# AgnusAdaptorv2.net
KiCad netlist of a schematic drawn in EAGLE
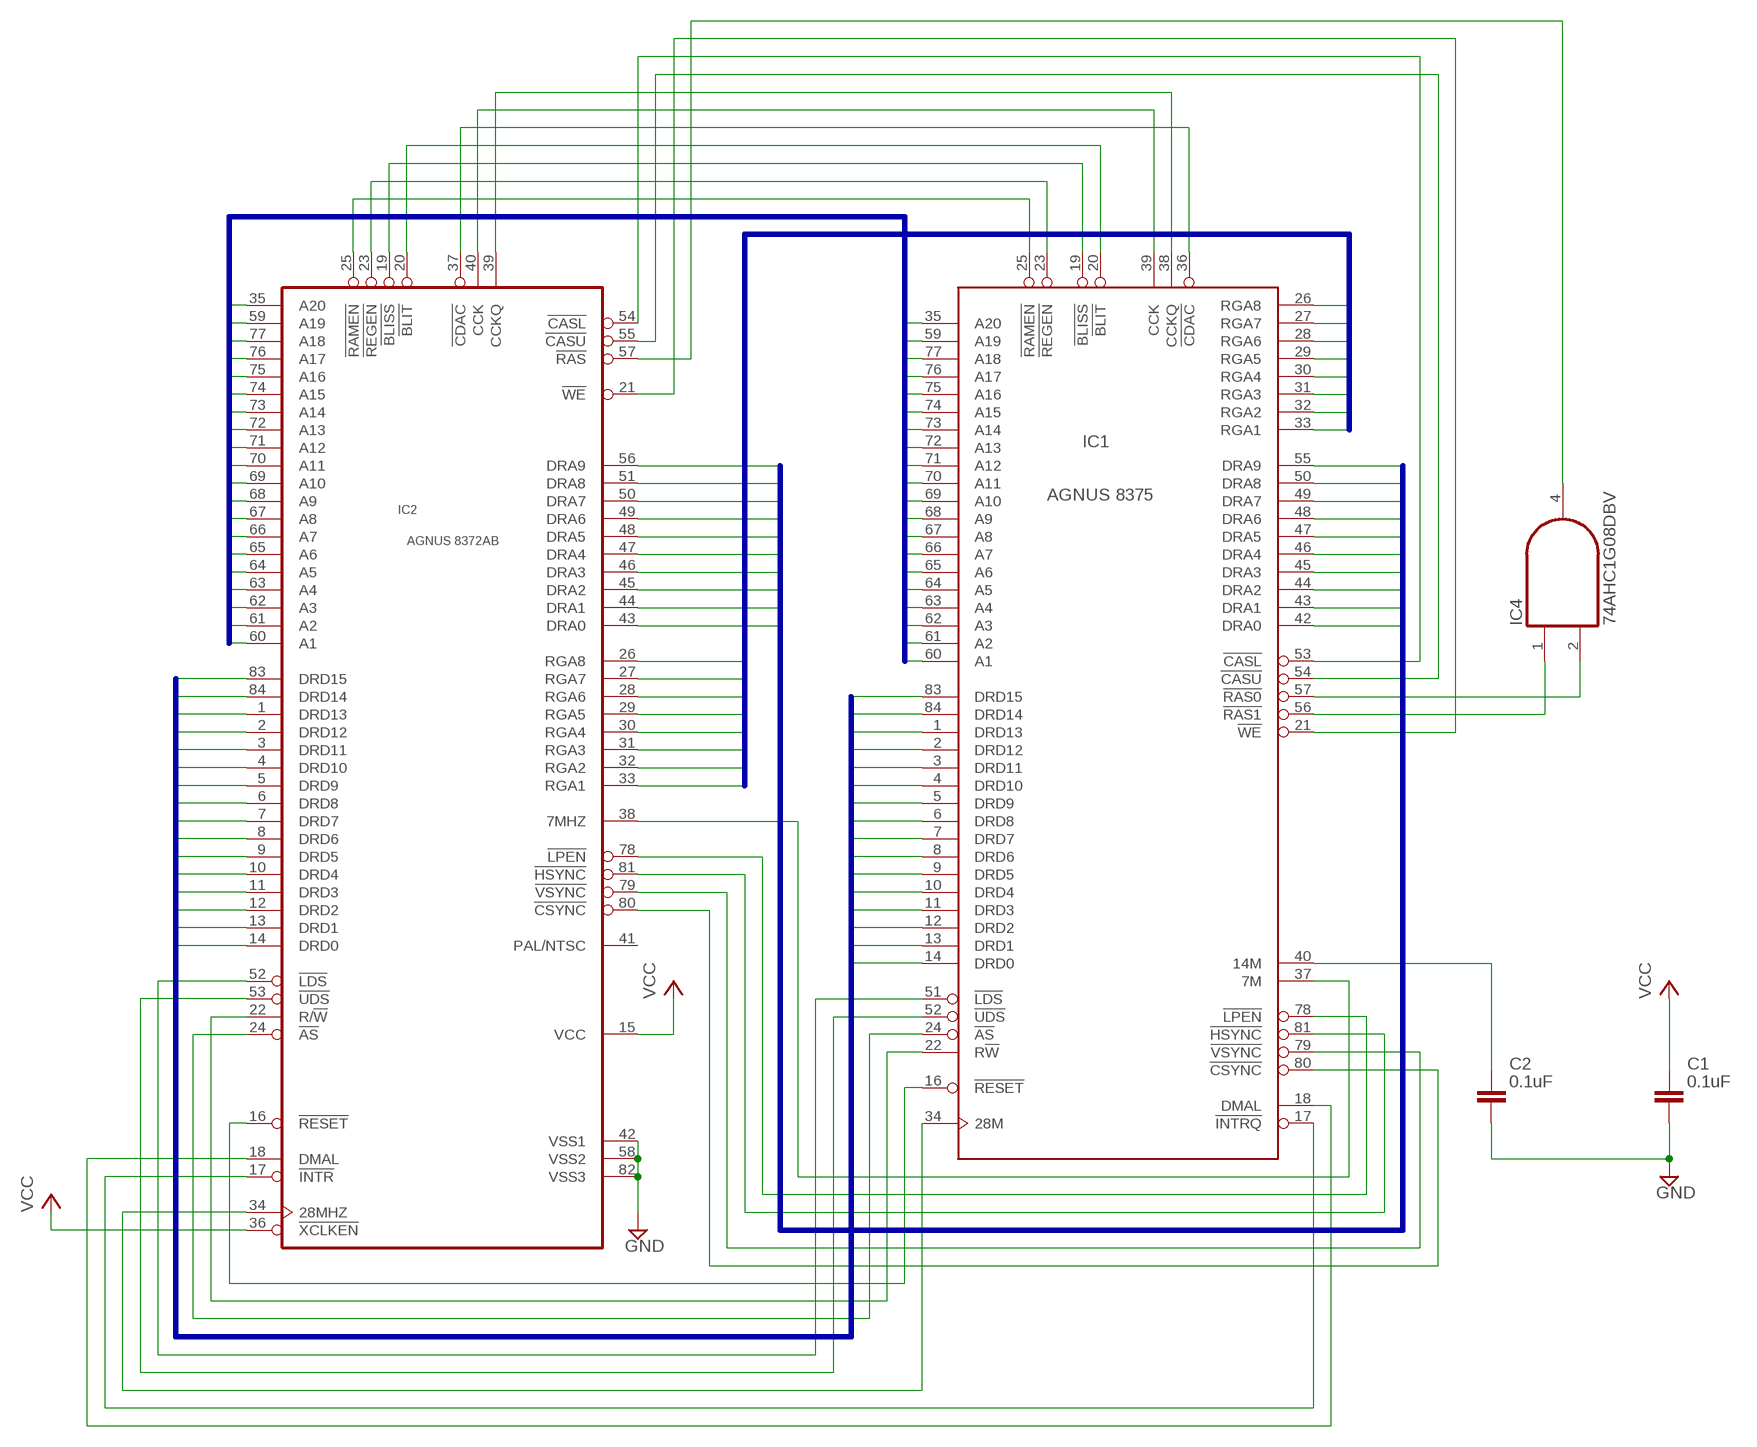
[diagram p0: schematic, sheet 1]

(export (version "E")
  (design (tool "Eeschema 10.0.6"))
  (components
    (comp (ref "C1")
      (value "0.1uF")
      (footprint "eagle-import:CAPC2012X110")
      (libsource (lib "eagle-import") (part "CCHIP-0805(2012-METRIC)_"))
    )
    (comp (ref "C2")
      (value "0.1uF")
      (footprint "eagle-import:CAPC2012X110")
      (libsource (lib "eagle-import") (part "CCHIP-0805(2012-METRIC)_"))
    )
    (comp (ref "IC1")
      (value "AGNUS_8375_A500+_A600_THT")
      (footprint "eagle-import:PLCC84_T")
      (fields (field (name "SPICEPREFIX") "X"))
      (libsource (lib "eagle-import") (part "AGNUS_8375_A500+_A600_THT"))
    )
    (comp (ref "IC2")
      (value "A3000 Agnus Socket")
      (footprint "eagle-import:PLCC84_T_H")
      (libsource (lib "eagle-import") (part "AGNUS_8372AB_THT_HDR"))
    )
    (comp (ref "IC4")
      (value "74AHC1G08DBV")
      (footprint "eagle-import:SOT23-5")
      (libsource (lib "eagle-import") (part "741G08DBVAHC"))
    )
  )
  (nets
    (net (code "1") (name "/A1") (class "Default")
      (node (ref "IC1") (pin "60") (pinfunction "A1_60") (pintype "input"))
      (node (ref "IC2") (pin "60") (pinfunction "A1_60") (pintype "input"))
    )
    (net (code "2") (name "/A2") (class "Default")
      (node (ref "IC1") (pin "61") (pinfunction "A2_61") (pintype "input"))
      (node (ref "IC2") (pin "61") (pinfunction "A2_61") (pintype "input"))
    )
    (net (code "3") (name "/A3") (class "Default")
      (node (ref "IC1") (pin "62") (pinfunction "A3_62") (pintype "input"))
      (node (ref "IC2") (pin "62") (pinfunction "A3_62") (pintype "input"))
    )
    (net (code "4") (name "/A4") (class "Default")
      (node (ref "IC1") (pin "63") (pinfunction "A4_63") (pintype "input"))
      (node (ref "IC2") (pin "63") (pinfunction "A4_63") (pintype "input"))
    )
    (net (code "5") (name "/A5") (class "Default")
      (node (ref "IC1") (pin "64") (pinfunction "A5_64") (pintype "input"))
      (node (ref "IC2") (pin "64") (pinfunction "A5_64") (pintype "input"))
    )
    (net (code "6") (name "/A6") (class "Default")
      (node (ref "IC1") (pin "65") (pinfunction "A6_65") (pintype "input"))
      (node (ref "IC2") (pin "65") (pinfunction "A6_65") (pintype "input"))
    )
    (net (code "7") (name "/A7") (class "Default")
      (node (ref "IC1") (pin "66") (pinfunction "A7_66") (pintype "input"))
      (node (ref "IC2") (pin "66") (pinfunction "A7_66") (pintype "input"))
    )
    (net (code "8") (name "/A8") (class "Default")
      (node (ref "IC1") (pin "67") (pinfunction "A8_67") (pintype "input"))
      (node (ref "IC2") (pin "67") (pinfunction "A8_67") (pintype "input"))
    )
    (net (code "9") (name "/A9") (class "Default")
      (node (ref "IC1") (pin "68") (pinfunction "A9_68") (pintype "input"))
      (node (ref "IC2") (pin "68") (pinfunction "A9_68") (pintype "input"))
    )
    (net (code "10") (name "/A10") (class "Default")
      (node (ref "IC1") (pin "69") (pinfunction "A10_69") (pintype "input"))
      (node (ref "IC2") (pin "69") (pinfunction "A10_69") (pintype "input"))
    )
    (net (code "11") (name "/A11") (class "Default")
      (node (ref "IC1") (pin "70") (pinfunction "A11_70") (pintype "input"))
      (node (ref "IC2") (pin "70") (pinfunction "A11_70") (pintype "input"))
    )
    (net (code "12") (name "/A12") (class "Default")
      (node (ref "IC1") (pin "71") (pinfunction "A12_71") (pintype "input"))
      (node (ref "IC2") (pin "71") (pinfunction "A12_71") (pintype "input"))
    )
    (net (code "13") (name "/A13") (class "Default")
      (node (ref "IC1") (pin "72") (pinfunction "A13_72") (pintype "input"))
      (node (ref "IC2") (pin "72") (pinfunction "A13_72") (pintype "input"))
    )
    (net (code "14") (name "/A14") (class "Default")
      (node (ref "IC1") (pin "73") (pinfunction "A14_73") (pintype "input"))
      (node (ref "IC2") (pin "73") (pinfunction "A14_73") (pintype "input"))
    )
    (net (code "15") (name "/A15") (class "Default")
      (node (ref "IC1") (pin "74") (pinfunction "A15_74") (pintype "input"))
      (node (ref "IC2") (pin "74") (pinfunction "A15_74") (pintype "input"))
    )
    (net (code "16") (name "/A16") (class "Default")
      (node (ref "IC1") (pin "75") (pinfunction "A16_75") (pintype "input"))
      (node (ref "IC2") (pin "75") (pinfunction "A16_75") (pintype "input"))
    )
    (net (code "17") (name "/A17") (class "Default")
      (node (ref "IC1") (pin "76") (pinfunction "A17_76") (pintype "input"))
      (node (ref "IC2") (pin "76") (pinfunction "A17_76") (pintype "input"))
    )
    (net (code "18") (name "/A18") (class "Default")
      (node (ref "IC1") (pin "77") (pinfunction "A18_77") (pintype "input"))
      (node (ref "IC2") (pin "77") (pinfunction "A18_77") (pintype "input"))
    )
    (net (code "19") (name "/A19") (class "Default")
      (node (ref "IC1") (pin "59") (pinfunction "A19_59") (pintype "input"))
      (node (ref "IC2") (pin "59") (pinfunction "A19_59") (pintype "input"))
    )
    (net (code "20") (name "/A20") (class "Default")
      (node (ref "IC1") (pin "35") (pinfunction "A20_35") (pintype "input"))
      (node (ref "IC2") (pin "35") (pinfunction "A20_35") (pintype "input"))
    )
    (net (code "21") (name "/DRA0") (class "Default")
      (node (ref "IC1") (pin "42") (pinfunction "DRA0_42") (pintype "output"))
      (node (ref "IC2") (pin "43") (pinfunction "DRA0_43") (pintype "output"))
    )
    (net (code "22") (name "/DRA1") (class "Default")
      (node (ref "IC1") (pin "43") (pinfunction "DRA1_43") (pintype "output"))
      (node (ref "IC2") (pin "44") (pinfunction "DRA1_44") (pintype "output"))
    )
    (net (code "23") (name "/DRA2") (class "Default")
      (node (ref "IC1") (pin "44") (pinfunction "DRA2_44") (pintype "output"))
      (node (ref "IC2") (pin "45") (pinfunction "DRA2_45") (pintype "output"))
    )
    (net (code "24") (name "/DRA3") (class "Default")
      (node (ref "IC1") (pin "45") (pinfunction "DRA3_45") (pintype "output"))
      (node (ref "IC2") (pin "46") (pinfunction "DRA3_46") (pintype "output"))
    )
    (net (code "25") (name "/DRA4") (class "Default")
      (node (ref "IC1") (pin "46") (pinfunction "DRA4_46") (pintype "output"))
      (node (ref "IC2") (pin "47") (pinfunction "DRA4_47") (pintype "output"))
    )
    (net (code "26") (name "/DRA5") (class "Default")
      (node (ref "IC1") (pin "47") (pinfunction "DRA5_47") (pintype "output"))
      (node (ref "IC2") (pin "48") (pinfunction "DRA5_48") (pintype "output"))
    )
    (net (code "27") (name "/DRA6") (class "Default")
      (node (ref "IC1") (pin "48") (pinfunction "DRA6_48") (pintype "output"))
      (node (ref "IC2") (pin "49") (pinfunction "DRA6_49") (pintype "output"))
    )
    (net (code "28") (name "/DRA7") (class "Default")
      (node (ref "IC1") (pin "49") (pinfunction "DRA7_49") (pintype "output"))
      (node (ref "IC2") (pin "50") (pinfunction "DRA7_50") (pintype "output"))
    )
    (net (code "29") (name "/DRA8") (class "Default")
      (node (ref "IC1") (pin "50") (pinfunction "DRA8_50") (pintype "output"))
      (node (ref "IC2") (pin "51") (pinfunction "DRA8_51") (pintype "output"))
    )
    (net (code "30") (name "/DRA9") (class "Default")
      (node (ref "IC1") (pin "55") (pinfunction "DRA9_55") (pintype "output"))
      (node (ref "IC2") (pin "56") (pinfunction "DRA9_56") (pintype "output"))
    )
    (net (code "31") (name "/DRD0") (class "Default")
      (node (ref "IC1") (pin "14") (pinfunction "DRD0_14") (pintype "bidirectional"))
      (node (ref "IC2") (pin "14") (pinfunction "DRD0_14") (pintype "bidirectional"))
    )
    (net (code "32") (name "/DRD1") (class "Default")
      (node (ref "IC1") (pin "13") (pinfunction "DRD1_13") (pintype "bidirectional"))
      (node (ref "IC2") (pin "13") (pinfunction "DRD1_13") (pintype "bidirectional"))
    )
    (net (code "33") (name "/DRD2") (class "Default")
      (node (ref "IC1") (pin "12") (pinfunction "DRD2_12") (pintype "bidirectional"))
      (node (ref "IC2") (pin "12") (pinfunction "DRD2_12") (pintype "bidirectional"))
    )
    (net (code "34") (name "/DRD3") (class "Default")
      (node (ref "IC1") (pin "11") (pinfunction "DRD3_11") (pintype "bidirectional"))
      (node (ref "IC2") (pin "11") (pinfunction "DRD3_11") (pintype "bidirectional"))
    )
    (net (code "35") (name "/DRD4") (class "Default")
      (node (ref "IC1") (pin "10") (pinfunction "DRD4_10") (pintype "bidirectional"))
      (node (ref "IC2") (pin "10") (pinfunction "DRD4_10") (pintype "bidirectional"))
    )
    (net (code "36") (name "/DRD5") (class "Default")
      (node (ref "IC1") (pin "9") (pinfunction "DRD5_9") (pintype "bidirectional"))
      (node (ref "IC2") (pin "9") (pinfunction "DRD5_9") (pintype "bidirectional"))
    )
    (net (code "37") (name "/DRD6") (class "Default")
      (node (ref "IC1") (pin "8") (pinfunction "DRD6_8") (pintype "bidirectional"))
      (node (ref "IC2") (pin "8") (pinfunction "DRD6_8") (pintype "bidirectional"))
    )
    (net (code "38") (name "/DRD7") (class "Default")
      (node (ref "IC1") (pin "7") (pinfunction "DRD7_7") (pintype "bidirectional"))
      (node (ref "IC2") (pin "7") (pinfunction "DRD7_7") (pintype "bidirectional"))
    )
    (net (code "39") (name "/DRD8") (class "Default")
      (node (ref "IC1") (pin "6") (pinfunction "DRD8_6") (pintype "bidirectional"))
      (node (ref "IC2") (pin "6") (pinfunction "DRD8_6") (pintype "bidirectional"))
    )
    (net (code "40") (name "/DRD9") (class "Default")
      (node (ref "IC1") (pin "5") (pinfunction "DRD9_5") (pintype "bidirectional"))
      (node (ref "IC2") (pin "5") (pinfunction "DRD9_5") (pintype "bidirectional"))
    )
    (net (code "41") (name "/DRD10") (class "Default")
      (node (ref "IC1") (pin "4") (pinfunction "DRD10_4") (pintype "bidirectional"))
      (node (ref "IC2") (pin "4") (pinfunction "DRD10_4") (pintype "bidirectional"))
    )
    (net (code "42") (name "/DRD11") (class "Default")
      (node (ref "IC1") (pin "3") (pinfunction "DRD11_3") (pintype "bidirectional"))
      (node (ref "IC2") (pin "3") (pinfunction "DRD11_3") (pintype "bidirectional"))
    )
    (net (code "43") (name "/DRD12") (class "Default")
      (node (ref "IC1") (pin "2") (pinfunction "DRD12_2") (pintype "bidirectional"))
      (node (ref "IC2") (pin "2") (pinfunction "DRD12_2") (pintype "bidirectional"))
    )
    (net (code "44") (name "/DRD13") (class "Default")
      (node (ref "IC1") (pin "1") (pinfunction "DRD13_1") (pintype "bidirectional"))
      (node (ref "IC2") (pin "1") (pinfunction "DRD13_1") (pintype "bidirectional"))
    )
    (net (code "45") (name "/DRD14") (class "Default")
      (node (ref "IC1") (pin "84") (pinfunction "DRD14_84") (pintype "bidirectional"))
      (node (ref "IC2") (pin "84") (pinfunction "DRD14_84") (pintype "bidirectional"))
    )
    (net (code "46") (name "/DRD15") (class "Default")
      (node (ref "IC1") (pin "83") (pinfunction "DRD15_83") (pintype "bidirectional"))
      (node (ref "IC2") (pin "83") (pinfunction "DRD15_83") (pintype "bidirectional"))
    )
    (net (code "47") (name "/RGA1") (class "Default")
      (node (ref "IC1") (pin "33") (pinfunction "RGA1_33") (pintype "output"))
      (node (ref "IC2") (pin "33") (pinfunction "RGA1_33") (pintype "bidirectional"))
    )
    (net (code "48") (name "/RGA2") (class "Default")
      (node (ref "IC1") (pin "32") (pinfunction "RGA2_32") (pintype "output"))
      (node (ref "IC2") (pin "32") (pinfunction "RGA2_32") (pintype "bidirectional"))
    )
    (net (code "49") (name "/RGA3") (class "Default")
      (node (ref "IC1") (pin "31") (pinfunction "RGA3_31") (pintype "output"))
      (node (ref "IC2") (pin "31") (pinfunction "RGA3_31") (pintype "bidirectional"))
    )
    (net (code "50") (name "/RGA4") (class "Default")
      (node (ref "IC1") (pin "30") (pinfunction "RGA4_30") (pintype "output"))
      (node (ref "IC2") (pin "30") (pinfunction "RGA4_30") (pintype "bidirectional"))
    )
    (net (code "51") (name "/RGA5") (class "Default")
      (node (ref "IC1") (pin "29") (pinfunction "RGA5_29") (pintype "output"))
      (node (ref "IC2") (pin "29") (pinfunction "RGA5_29") (pintype "bidirectional"))
    )
    (net (code "52") (name "/RGA6") (class "Default")
      (node (ref "IC1") (pin "28") (pinfunction "RGA6_28") (pintype "output"))
      (node (ref "IC2") (pin "28") (pinfunction "RGA6_28") (pintype "bidirectional"))
    )
    (net (code "53") (name "/RGA7") (class "Default")
      (node (ref "IC1") (pin "27") (pinfunction "RGA7_27") (pintype "output"))
      (node (ref "IC2") (pin "27") (pinfunction "RGA7_27") (pintype "bidirectional"))
    )
    (net (code "54") (name "/RGA8") (class "Default")
      (node (ref "IC1") (pin "26") (pinfunction "RGA8_26") (pintype "output"))
      (node (ref "IC2") (pin "26") (pinfunction "RGA8_26") (pintype "bidirectional"))
    )
    (net (code "55") (name "GND") (class "Default")
      (node (ref "C1") (pin "2") (pinfunction "2_2") (pintype "passive"))
      (node (ref "C2") (pin "2") (pinfunction "2_2") (pintype "passive"))
      (node (ref "IC2") (pin "42") (pinfunction "VSS1_42") (pintype "power_in"))
      (node (ref "IC2") (pin "58") (pinfunction "VSS2_58") (pintype "power_in"))
      (node (ref "IC2") (pin "82") (pinfunction "VSS3_82") (pintype "power_in"))
    )
    (net (code "56") (name "Net-(IC1A-7M)") (class "Default")
      (node (ref "IC1") (pin "37") (pinfunction "7M_37") (pintype "output"))
      (node (ref "IC2") (pin "38") (pinfunction "7MHZ_38") (pintype "output"))
    )
    (net (code "57") (name "Net-(IC1A-14M)") (class "Default")
      (node (ref "C2") (pin "1") (pinfunction "1_1") (pintype "passive"))
      (node (ref "IC1") (pin "40") (pinfunction "14M_40") (pintype "output"))
    )
    (net (code "58") (name "Net-(IC1A-28M)") (class "Default")
      (node (ref "IC1") (pin "34") (pinfunction "28M_34") (pintype "input"))
      (node (ref "IC2") (pin "34") (pinfunction "28MHZ_34") (pintype "input"))
    )
    (net (code "59") (name "Net-(IC1A-CCK)") (class "Default")
      (node (ref "IC1") (pin "39") (pinfunction "CCK_39") (pintype "output"))
      (node (ref "IC2") (pin "40") (pinfunction "CCK_40") (pintype "output"))
    )
    (net (code "60") (name "Net-(IC1A-CCKQ)") (class "Default")
      (node (ref "IC1") (pin "38") (pinfunction "CCKQ_38") (pintype "output"))
      (node (ref "IC2") (pin "39") (pinfunction "CCKQ_39") (pintype "output"))
    )
    (net (code "61") (name "Net-(IC1A-DMAL)") (class "Default")
      (node (ref "IC1") (pin "18") (pinfunction "DMAL_18") (pintype "input"))
      (node (ref "IC2") (pin "18") (pinfunction "DMAL_18") (pintype "input"))
    )
    (net (code "62") (name "Net-(IC1A-R~{W})") (class "Default")
      (node (ref "IC1") (pin "22") (pinfunction "R~{W}_22") (pintype "input"))
      (node (ref "IC2") (pin "22") (pinfunction "R/~{W}_22") (pintype "input"))
    )
    (net (code "63") (name "Net-(IC1A-~{AS})") (class "Default")
      (node (ref "IC1") (pin "24") (pinfunction "~{AS}_24") (pintype "input"))
      (node (ref "IC2") (pin "24") (pinfunction "~{AS}_24") (pintype "input"))
    )
    (net (code "64") (name "Net-(IC1A-~{BLISS})") (class "Default")
      (node (ref "IC1") (pin "19") (pinfunction "~{BLISS}_19") (pintype "output"))
      (node (ref "IC2") (pin "19") (pinfunction "~{BLISS}_19") (pintype "input"))
    )
    (net (code "65") (name "Net-(IC1A-~{BLIT})") (class "Default")
      (node (ref "IC1") (pin "20") (pinfunction "~{BLIT}_20") (pintype "output"))
      (node (ref "IC2") (pin "20") (pinfunction "~{BLIT}_20") (pintype "output"))
    )
    (net (code "66") (name "Net-(IC1A-~{CASL})") (class "Default")
      (node (ref "IC1") (pin "53") (pinfunction "~{CASL}_53") (pintype "output"))
      (node (ref "IC2") (pin "54") (pinfunction "~{CASL}_54") (pintype "output"))
    )
    (net (code "67") (name "Net-(IC1A-~{CASU})") (class "Default")
      (node (ref "IC1") (pin "54") (pinfunction "~{CASU}_54") (pintype "output"))
      (node (ref "IC2") (pin "55") (pinfunction "~{CASU}_55") (pintype "output"))
    )
    (net (code "68") (name "Net-(IC1A-~{CDAC})") (class "Default")
      (node (ref "IC1") (pin "36") (pinfunction "~{CDAC}_36") (pintype "output"))
      (node (ref "IC2") (pin "37") (pinfunction "~{CDAC}_37") (pintype "output"))
    )
    (net (code "69") (name "Net-(IC1A-~{CSYNC})") (class "Default")
      (node (ref "IC1") (pin "80") (pinfunction "~{CSYNC}_80") (pintype "output"))
      (node (ref "IC2") (pin "80") (pinfunction "~{CSYNC}_80") (pintype "output"))
    )
    (net (code "70") (name "Net-(IC1A-~{HSYNC})") (class "Default")
      (node (ref "IC1") (pin "81") (pinfunction "~{HSYNC}_81") (pintype "output"))
      (node (ref "IC2") (pin "81") (pinfunction "~{HSYNC}_81") (pintype "output"))
    )
    (net (code "71") (name "Net-(IC1A-~{INTRQ})") (class "Default")
      (node (ref "IC1") (pin "17") (pinfunction "~{INTRQ}_17") (pintype "output"))
      (node (ref "IC2") (pin "17") (pinfunction "~{INTR}_17") (pintype "output"))
    )
    (net (code "72") (name "Net-(IC1A-~{LDS})") (class "Default")
      (node (ref "IC1") (pin "51") (pinfunction "~{LDS}_51") (pintype "input"))
      (node (ref "IC2") (pin "52") (pinfunction "~{LDS}_52") (pintype "input"))
    )
    (net (code "73") (name "Net-(IC1A-~{LPEN})") (class "Default")
      (node (ref "IC1") (pin "78") (pinfunction "~{LPEN}_78") (pintype "input"))
      (node (ref "IC2") (pin "78") (pinfunction "~{LPEN}_78") (pintype "input"))
    )
    (net (code "74") (name "Net-(IC1A-~{RAMEN})") (class "Default")
      (node (ref "IC1") (pin "25") (pinfunction "~{RAMEN}_25") (pintype "output"))
      (node (ref "IC2") (pin "25") (pinfunction "~{RAMEN}_25") (pintype "input"))
    )
    (net (code "75") (name "Net-(IC1A-~{RAS0})") (class "Default")
      (node (ref "IC1") (pin "57") (pinfunction "~{RAS0}_57") (pintype "output"))
      (node (ref "IC4") (pin "2") (pinfunction "I1_2") (pintype "input"))
    )
    (net (code "76") (name "Net-(IC1A-~{RAS1})") (class "Default")
      (node (ref "IC1") (pin "56") (pinfunction "~{RAS1}_56") (pintype "output"))
      (node (ref "IC4") (pin "1") (pinfunction "I0_1") (pintype "input"))
    )
    (net (code "77") (name "Net-(IC1A-~{REGEN})") (class "Default")
      (node (ref "IC1") (pin "23") (pinfunction "~{REGEN}_23") (pintype "output"))
      (node (ref "IC2") (pin "23") (pinfunction "~{REGEN}_23") (pintype "input"))
    )
    (net (code "78") (name "Net-(IC1A-~{RESET})") (class "Default")
      (node (ref "IC1") (pin "16") (pinfunction "~{RESET}_16") (pintype "input"))
      (node (ref "IC2") (pin "16") (pinfunction "~{RESET}_16") (pintype "input"))
    )
    (net (code "79") (name "Net-(IC1A-~{UDS})") (class "Default")
      (node (ref "IC1") (pin "52") (pinfunction "~{UDS}_52") (pintype "input"))
      (node (ref "IC2") (pin "53") (pinfunction "~{UDS}_53") (pintype "input"))
    )
    (net (code "80") (name "Net-(IC1A-~{VSYNC})") (class "Default")
      (node (ref "IC1") (pin "79") (pinfunction "~{VSYNC}_79") (pintype "output"))
      (node (ref "IC2") (pin "79") (pinfunction "~{VSYNC}_79") (pintype "output"))
    )
    (net (code "81") (name "Net-(IC1A-~{WE})") (class "Default")
      (node (ref "IC1") (pin "21") (pinfunction "~{WE}_21") (pintype "output"))
      (node (ref "IC2") (pin "21") (pinfunction "~{WE}_21") (pintype "output"))
    )
    (net (code "82") (name "Net-(IC2-~{RAS})") (class "Default")
      (node (ref "IC2") (pin "57") (pinfunction "~{RAS}_57") (pintype "output"))
      (node (ref "IC4") (pin "4") (pinfunction "O_4") (pintype "output"))
    )
    (net (code "83") (name "VCC") (class "Default")
      (node (ref "C1") (pin "1") (pinfunction "1_1") (pintype "passive"))
      (node (ref "IC2") (pin "15") (pinfunction "VCC_15") (pintype "power_in"))
      (node (ref "IC2") (pin "36") (pinfunction "~{XCLKEN}_36") (pintype "input"))
    )
    (net (code "84") (name "unconnected-(IC2-PAL{slash}NTSC-Pad41)") (class "Default")
      (node (ref "IC2") (pin "41") (pinfunction "PAL/NTSC_41") (pintype "input"))
    )
  )
)
